# 04-RFID.net
KiCad netlist of a schematic drawn in Altium Designer
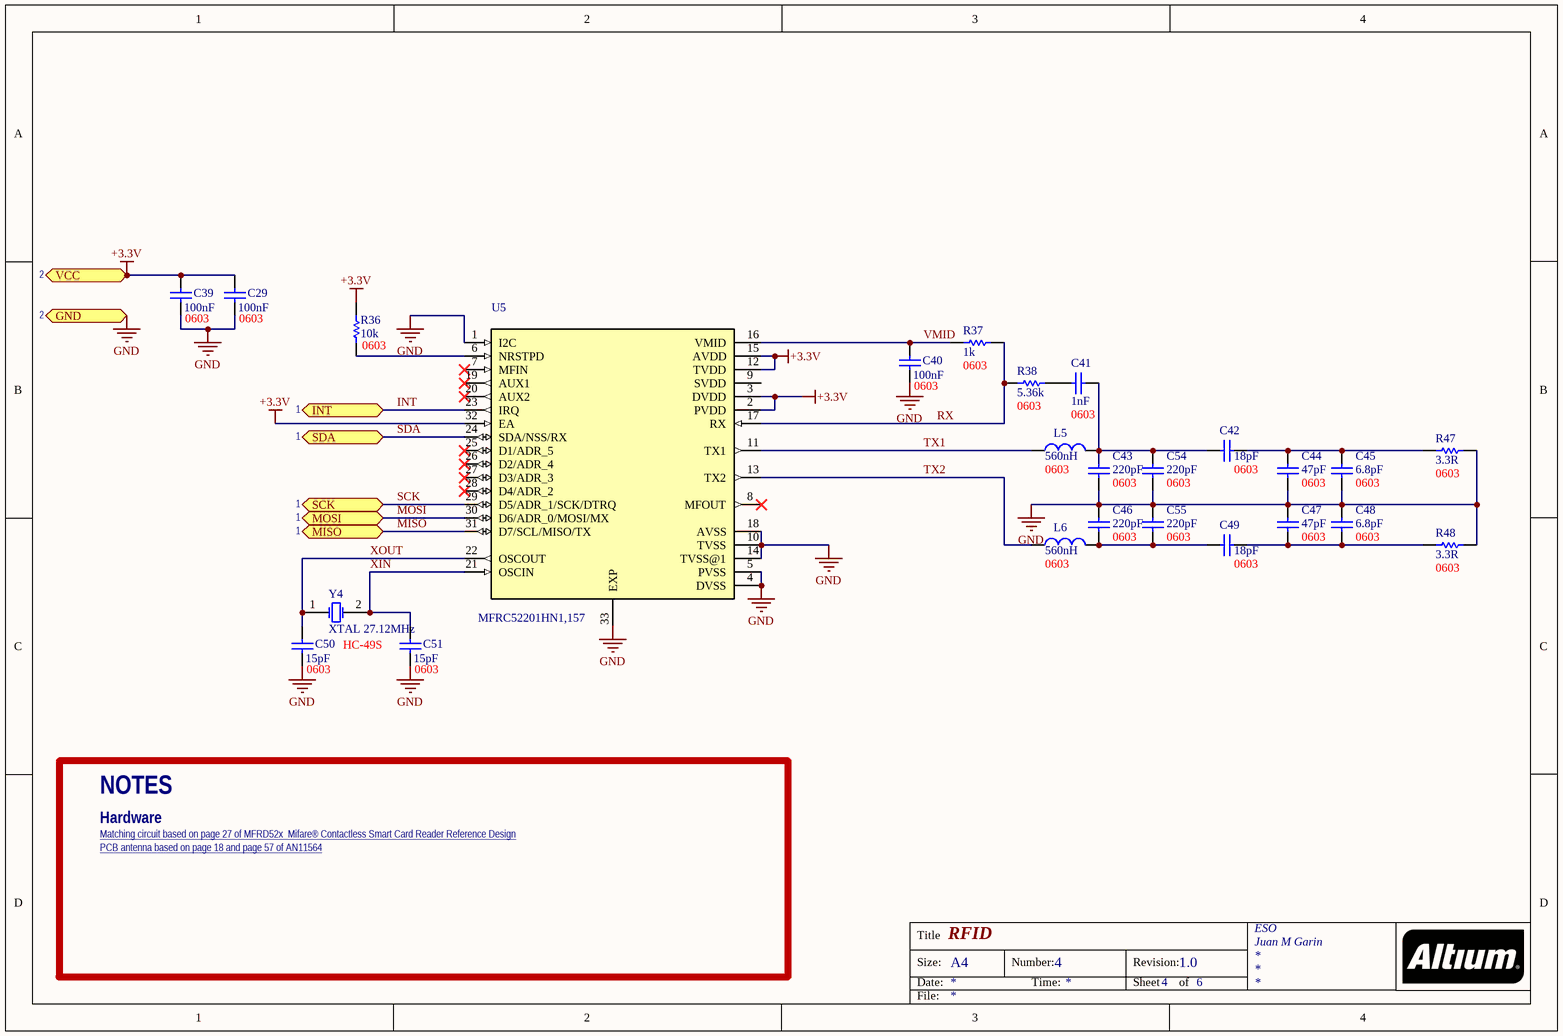
[diagram p0: 04-RFID.SchDoc]

(export (version "E")
  (design (tool "Eeschema 10.0.6"))
  (components
    (comp (ref "C29")
      (value "100nF")
      (footprint "C0603")
      (description "Capacitor (Semiconductor SIM Model)")
      (fields
        (field (name "MANUFACTURER PART NUMBER") "CL10F104ZO8NNNC")
        (field (name "PACKAGEREFERENCE") "0603")
      )
      (libsource (lib "Miscellaneous Devices") (part "Cap Semi"))
    )
    (comp (ref "C39")
      (value "100nF")
      (footprint "C0603")
      (description "Capacitor (Semiconductor SIM Model)")
      (fields
        (field (name "MANUFACTURER PART NUMBER") "CL10F104ZO8NNNC")
        (field (name "PACKAGEREFERENCE") "0603")
      )
      (libsource (lib "Miscellaneous Devices") (part "Cap Semi"))
    )
    (comp (ref "C40")
      (value "100nF")
      (footprint "C0603")
      (description "Capacitor (Semiconductor SIM Model)")
      (fields
        (field (name "MANUFACTURER PART NUMBER") "CL10F104ZO8NNNC")
        (field (name "PACKAGEREFERENCE") "0603")
      )
      (libsource (lib "Miscellaneous Devices") (part "Cap Semi"))
    )
    (comp (ref "C41")
      (value "1nF")
      (footprint "C0603")
      (description "Capacitor (Semiconductor SIM Model)")
      (fields
        (field (name "MANUFACTURER PART NUMBER") "CL10B102JB8NNNC")
        (field (name "PACKAGEREFERENCE") "0603")
      )
      (libsource (lib "Miscellaneous Devices") (part "Cap Semi"))
    )
    (comp (ref "C42")
      (value "18pF")
      (footprint "C0603")
      (description "Capacitor (Semiconductor SIM Model)")
      (fields
        (field (name "MANUFACTURER PART NUMBER") "VJ0603A180JXACW1BC")
        (field (name "PACKAGEREFERENCE") "0603")
      )
      (libsource (lib "Miscellaneous Devices") (part "Cap Semi"))
    )
    (comp (ref "C43")
      (value "220pF")
      (footprint "C0603")
      (description "Capacitor (Semiconductor SIM Model)")
      (fields
        (field (name "MANUFACTURER PART NUMBER") "885012206030")
        (field (name "PACKAGEREFERENCE") "0603")
      )
      (libsource (lib "Miscellaneous Devices") (part "Cap Semi"))
    )
    (comp (ref "C44")
      (value "47pF")
      (footprint "C0603")
      (description "Capacitor (Semiconductor SIM Model)")
      (fields
        (field (name "MANUFACTURER PART NUMBER") "885012006021")
        (field (name "PACKAGEREFERENCE") "0603")
      )
      (libsource (lib "Miscellaneous Devices") (part "Cap Semi"))
    )
    (comp (ref "C45")
      (value "6.8pF")
      (footprint "C0603")
      (description "Capacitor (Semiconductor SIM Model)")
      (fields
        (field (name "MANUFACTURER PART NUMBER") "CL10C6R8DB8NNNC")
        (field (name "PACKAGEREFERENCE") "0603")
      )
      (libsource (lib "Miscellaneous Devices") (part "Cap Semi"))
    )
    (comp (ref "C46")
      (value "220pF")
      (footprint "C0603")
      (description "Capacitor (Semiconductor SIM Model)")
      (fields
        (field (name "MANUFACTURER PART NUMBER") "885012206030")
        (field (name "PACKAGEREFERENCE") "0603")
      )
      (libsource (lib "Miscellaneous Devices") (part "Cap Semi"))
    )
    (comp (ref "C47")
      (value "47pF")
      (footprint "C0603")
      (description "Capacitor (Semiconductor SIM Model)")
      (fields
        (field (name "MANUFACTURER PART NUMBER") "885012006021")
        (field (name "PACKAGEREFERENCE") "0603")
      )
      (libsource (lib "Miscellaneous Devices") (part "Cap Semi"))
    )
    (comp (ref "C48")
      (value "6.8pF")
      (footprint "C0603")
      (description "Capacitor (Semiconductor SIM Model)")
      (fields
        (field (name "MANUFACTURER PART NUMBER") "CL10C6R8DB8NNNC")
        (field (name "PACKAGEREFERENCE") "0603")
      )
      (libsource (lib "Miscellaneous Devices") (part "Cap Semi"))
    )
    (comp (ref "C49")
      (value "18pF")
      (footprint "C0603")
      (description "Capacitor (Semiconductor SIM Model)")
      (fields
        (field (name "MANUFACTURER PART NUMBER") "VJ0603A180JXACW1BC")
        (field (name "PACKAGEREFERENCE") "0603")
      )
      (libsource (lib "Miscellaneous Devices") (part "Cap Semi"))
    )
    (comp (ref "C50")
      (value "15pF")
      (footprint "C0603")
      (description "Capacitor (Semiconductor SIM Model)")
      (fields
        (field (name "MANUFACTURER PART NUMBER") "CL10C150JC8NNNC")
        (field (name "PACKAGEREFERENCE") "0603")
      )
      (libsource (lib "Miscellaneous Devices") (part "Cap Semi"))
    )
    (comp (ref "C51")
      (value "15pF")
      (footprint "C0603")
      (description "Capacitor (Semiconductor SIM Model)")
      (fields
        (field (name "MANUFACTURER PART NUMBER") "CL10C150JC8NNNC")
        (field (name "PACKAGEREFERENCE") "0603")
      )
      (libsource (lib "Miscellaneous Devices") (part "Cap Semi"))
    )
    (comp (ref "C54")
      (value "220pF")
      (footprint "C0603")
      (description "Capacitor (Semiconductor SIM Model)")
      (fields
        (field (name "MANUFACTURER PART NUMBER") "885012206030")
        (field (name "PACKAGEREFERENCE") "0603")
      )
      (libsource (lib "Miscellaneous Devices") (part "Cap Semi"))
    )
    (comp (ref "C55")
      (value "220pF")
      (footprint "C0603")
      (description "Capacitor (Semiconductor SIM Model)")
      (fields
        (field (name "MANUFACTURER PART NUMBER") "885012206030")
        (field (name "PACKAGEREFERENCE") "0603")
      )
      (libsource (lib "Miscellaneous Devices") (part "Cap Semi"))
    )
    (comp (ref "L5")
      (value "560nH")
      (footprint "L0603")
      (description "Inductor")
      (fields
        (field (name "MANUFACTURER PART NUMBER") "AIML-0603-R56K-T")
        (field (name "PACKAGEREFERENCE") "0603")
      )
      (libsource (lib "schematic_library") (part "Inductor_0603"))
    )
    (comp (ref "L6")
      (value "560nH")
      (footprint "L0603")
      (description "Inductor")
      (fields
        (field (name "MANUFACTURER PART NUMBER") "AIML-0603-R56K-T")
        (field (name "PACKAGEREFERENCE") "0603")
      )
      (libsource (lib "schematic_library") (part "Inductor_0603"))
    )
    (comp (ref "R36")
      (value "10k")
      (footprint "R0603")
      (description "Resistor")
      (fields
        (field (name "MANUFACTURER PART NUMBER") "RMCF0603FT10K0")
        (field (name "PACKAGEREFERENCE") "0603")
      )
      (libsource (lib "Miscellaneous Devices") (part "Res1"))
    )
    (comp (ref "R37")
      (value "1k")
      (footprint "R0603")
      (description "Resistor")
      (fields
        (field (name "MANUFACTURER PART NUMBER") "RMCF0603FG1K00")
        (field (name "PACKAGEREFERENCE") "0603")
      )
      (libsource (lib "Miscellaneous Devices") (part "Res1"))
    )
    (comp (ref "R38")
      (value "5.36k")
      (footprint "R0603")
      (description "Resistor")
      (fields
        (field (name "MANUFACTURER PART NUMBER") "CR0603-FX-5361ELF")
        (field (name "PACKAGEREFERENCE") "0603")
      )
      (libsource (lib "Miscellaneous Devices") (part "Res1"))
    )
    (comp (ref "R47")
      (value "3.3R")
      (footprint "R0603")
      (description "Resistor")
      (fields
        (field (name "MANUFACTURER PART NUMBER") "CRGCQ0603J3R3")
        (field (name "PACKAGEREFERENCE") "0603")
      )
      (libsource (lib "Miscellaneous Devices") (part "Res1"))
    )
    (comp (ref "R48")
      (value "3.3R")
      (footprint "R0603")
      (description "Resistor")
      (fields
        (field (name "MANUFACTURER PART NUMBER") "CRGCQ0603J3R3")
        (field (name "PACKAGEREFERENCE") "0603")
      )
      (libsource (lib "Miscellaneous Devices") (part "Res1"))
    )
    (comp (ref "U5")
      (value "MFRC52201HN1,157")
      (footprint "QFN-32_5x5_0.5")
      (description "MFRC52201 Series 2.5 V - 3.6 V 27.12 MHz IC Smart Card Reader - HVQFN-32")
      (fields (field (name "MF") "NXP Semiconductors"))
      (libsource (lib "Library") (part "MFRC52201HN1,157"))
    )
    (comp (ref "Y4")
      (value "XTAL 27.12MHz")
      (footprint "XTAL-SMD")
      (description "Crystal Oscillator 27.12MHz SMD")
      (fields
        (field (name "MANUFACTURER PART NUMBER") "9C-27.120MAAJ-T")
        (field (name "PACKAGEREFERENCE") "HC-49S")
      )
      (libsource (lib "Library_Scott") (part "XTAL 16MHz"))
    )
  )
  (nets
    (net (code "1") (name "+3.3V") (class "Default")
      (node (ref "C29") (pin "2") (pinfunction "2_2") (pintype "passive"))
      (node (ref "C39") (pin "2") (pinfunction "2_2") (pintype "passive"))
      (node (ref "R36") (pin "1") (pinfunction "1_1") (pintype "passive"))
      (node (ref "U5") (pin "12") (pinfunction "TVDD_12") (pintype "power_in"))
      (node (ref "U5") (pin "15") (pinfunction "AVDD_15") (pintype "power_in"))
      (node (ref "U5") (pin "2") (pinfunction "PVDD_2") (pintype "power_in"))
      (node (ref "U5") (pin "3") (pinfunction "DVDD_3") (pintype "power_in"))
      (node (ref "U5") (pin "32") (pinfunction "EA_32") (pintype "input"))
    )
    (net (code "2") (name "/INT") (class "Default")
      (node (ref "U5") (pin "23") (pinfunction "IRQ_23") (pintype "output"))
    )
    (net (code "3") (name "/MISO") (class "Default")
      (node (ref "U5") (pin "31") (pinfunction "D7/SCL/MISO/TX_31") (pintype "bidirectional"))
    )
    (net (code "4") (name "/MOSI") (class "Default")
      (node (ref "U5") (pin "30") (pinfunction "D6/ADR_0/MOSI/MX_30") (pintype "bidirectional"))
    )
    (net (code "5") (name "/RX") (class "Default")
      (node (ref "R37") (pin "2") (pinfunction "2_2") (pintype "passive"))
      (node (ref "R38") (pin "1") (pinfunction "1_1") (pintype "passive"))
      (node (ref "U5") (pin "17") (pinfunction "RX_17") (pintype "input"))
    )
    (net (code "6") (name "/SCK") (class "Default")
      (node (ref "U5") (pin "29") (pinfunction "D5/ADR_1/SCK/DTRQ_29") (pintype "bidirectional"))
    )
    (net (code "7") (name "/SDA") (class "Default")
      (node (ref "U5") (pin "24") (pinfunction "SDA/NSS/RX_24") (pintype "bidirectional"))
    )
    (net (code "8") (name "/TX1") (class "Default")
      (node (ref "L5") (pin "1") (pinfunction "1_1") (pintype "passive"))
      (node (ref "U5") (pin "11") (pinfunction "TX1_11") (pintype "output"))
    )
    (net (code "9") (name "/TX2") (class "Default")
      (node (ref "L6") (pin "1") (pinfunction "1_1") (pintype "passive"))
      (node (ref "U5") (pin "13") (pinfunction "TX2_13") (pintype "output"))
    )
    (net (code "10") (name "/VMID") (class "Default")
      (node (ref "C40") (pin "2") (pinfunction "2_2") (pintype "passive"))
      (node (ref "R37") (pin "1") (pinfunction "1_1") (pintype "passive"))
      (node (ref "U5") (pin "16") (pinfunction "VMID_16") (pintype "power_in"))
    )
    (net (code "11") (name "/XIN") (class "Default")
      (node (ref "C51") (pin "2") (pinfunction "2_2") (pintype "passive"))
      (node (ref "U5") (pin "21") (pinfunction "OSCIN_21") (pintype "input"))
      (node (ref "Y4") (pin "2") (pinfunction "OSC2_2") (pintype "passive"))
    )
    (net (code "12") (name "/XOUT") (class "Default")
      (node (ref "C50") (pin "2") (pinfunction "2_2") (pintype "passive"))
      (node (ref "U5") (pin "22") (pinfunction "OSCOUT_22") (pintype "output"))
      (node (ref "Y4") (pin "1") (pinfunction "OSC1_1") (pintype "passive"))
    )
    (net (code "13") (name "GND") (class "Default")
      (node (ref "C29") (pin "1") (pinfunction "1_1") (pintype "passive"))
      (node (ref "C39") (pin "1") (pinfunction "1_1") (pintype "passive"))
      (node (ref "C40") (pin "1") (pinfunction "1_1") (pintype "passive"))
      (node (ref "C43") (pin "2") (pinfunction "2_2") (pintype "passive"))
      (node (ref "C44") (pin "2") (pinfunction "2_2") (pintype "passive"))
      (node (ref "C45") (pin "2") (pinfunction "2_2") (pintype "passive"))
      (node (ref "C46") (pin "1") (pinfunction "1_1") (pintype "passive"))
      (node (ref "C47") (pin "1") (pinfunction "1_1") (pintype "passive"))
      (node (ref "C48") (pin "1") (pinfunction "1_1") (pintype "passive"))
      (node (ref "C50") (pin "1") (pinfunction "1_1") (pintype "passive"))
      (node (ref "C51") (pin "1") (pinfunction "1_1") (pintype "passive"))
      (node (ref "C54") (pin "2") (pinfunction "2_2") (pintype "passive"))
      (node (ref "C55") (pin "1") (pinfunction "1_1") (pintype "passive"))
      (node (ref "R47") (pin "2") (pinfunction "2_2") (pintype "passive"))
      (node (ref "R48") (pin "2") (pinfunction "2_2") (pintype "passive"))
      (node (ref "U5") (pin "1") (pinfunction "I2C_1") (pintype "input"))
      (node (ref "U5") (pin "10") (pinfunction "TVSS_10") (pintype "power_in"))
      (node (ref "U5") (pin "14") (pinfunction "TVSS@1_14") (pintype "power_in"))
      (node (ref "U5") (pin "18") (pinfunction "AVSS_18") (pintype "power_in"))
      (node (ref "U5") (pin "33") (pinfunction "EXP_33") (pintype "power_in"))
      (node (ref "U5") (pin "4") (pinfunction "DVSS_4") (pintype "power_in"))
      (node (ref "U5") (pin "5") (pinfunction "PVSS_5") (pintype "power_in"))
    )
    (net (code "14") (name "Net-(C41-Pad1)") (class "Default")
      (node (ref "C41") (pin "1") (pinfunction "1_1") (pintype "passive"))
      (node (ref "C42") (pin "2") (pinfunction "2_2") (pintype "passive"))
      (node (ref "C43") (pin "1") (pinfunction "1_1") (pintype "passive"))
      (node (ref "C54") (pin "1") (pinfunction "1_1") (pintype "passive"))
      (node (ref "L5") (pin "2") (pinfunction "2_2") (pintype "passive"))
    )
    (net (code "15") (name "Net-(C41-Pad2)") (class "Default")
      (node (ref "C41") (pin "2") (pinfunction "2_2") (pintype "passive"))
      (node (ref "R38") (pin "2") (pinfunction "2_2") (pintype "passive"))
    )
    (net (code "16") (name "Net-(C42-Pad1)") (class "Default")
      (node (ref "C42") (pin "1") (pinfunction "1_1") (pintype "passive"))
      (node (ref "C44") (pin "1") (pinfunction "1_1") (pintype "passive"))
      (node (ref "C45") (pin "1") (pinfunction "1_1") (pintype "passive"))
      (node (ref "R47") (pin "1") (pinfunction "1_1") (pintype "passive"))
    )
    (net (code "17") (name "Net-(C46-Pad2)") (class "Default")
      (node (ref "C46") (pin "2") (pinfunction "2_2") (pintype "passive"))
      (node (ref "C49") (pin "2") (pinfunction "2_2") (pintype "passive"))
      (node (ref "C55") (pin "2") (pinfunction "2_2") (pintype "passive"))
      (node (ref "L6") (pin "2") (pinfunction "2_2") (pintype "passive"))
    )
    (net (code "18") (name "Net-(C47-Pad2)") (class "Default")
      (node (ref "C47") (pin "2") (pinfunction "2_2") (pintype "passive"))
      (node (ref "C48") (pin "2") (pinfunction "2_2") (pintype "passive"))
      (node (ref "C49") (pin "1") (pinfunction "1_1") (pintype "passive"))
      (node (ref "R48") (pin "1") (pinfunction "1_1") (pintype "passive"))
    )
    (net (code "19") (name "Net-(U5-NRSTPD)") (class "Default")
      (node (ref "R36") (pin "2") (pinfunction "2_2") (pintype "passive"))
      (node (ref "U5") (pin "6") (pinfunction "NRSTPD_6") (pintype "input"))
    )
    (net (code "20") (name "unconnected-(U5-AUX1-Pad19)") (class "Default")
      (node (ref "U5") (pin "19") (pinfunction "AUX1_19") (pintype "output+no_connect"))
    )
    (net (code "21") (name "unconnected-(U5-AUX2-Pad20)") (class "Default")
      (node (ref "U5") (pin "20") (pinfunction "AUX2_20") (pintype "output+no_connect"))
    )
    (net (code "22") (name "unconnected-(U5-D1{slash}ADR_5-Pad25)") (class "Default")
      (node (ref "U5") (pin "25") (pinfunction "D1/ADR_5_25") (pintype "bidirectional+no_connect"))
    )
    (net (code "23") (name "unconnected-(U5-D2{slash}ADR_4-Pad26)") (class "Default")
      (node (ref "U5") (pin "26") (pinfunction "D2/ADR_4_26") (pintype "bidirectional+no_connect"))
    )
    (net (code "24") (name "unconnected-(U5-D3{slash}ADR_3-Pad27)") (class "Default")
      (node (ref "U5") (pin "27") (pinfunction "D3/ADR_3_27") (pintype "bidirectional+no_connect"))
    )
    (net (code "25") (name "unconnected-(U5-D4{slash}ADR_2-Pad28)") (class "Default")
      (node (ref "U5") (pin "28") (pinfunction "D4/ADR_2_28") (pintype "bidirectional+no_connect"))
    )
    (net (code "26") (name "unconnected-(U5-MFIN-Pad7)") (class "Default")
      (node (ref "U5") (pin "7") (pinfunction "MFIN_7") (pintype "input+no_connect"))
    )
    (net (code "27") (name "unconnected-(U5-MFOUT-Pad8)") (class "Default")
      (node (ref "U5") (pin "8") (pinfunction "MFOUT_8") (pintype "output+no_connect"))
    )
    (net (code "28") (name "unconnected-(U5-SVDD-Pad9)") (class "Default")
      (node (ref "U5") (pin "9") (pinfunction "SVDD_9") (pintype "power_in"))
    )
  )
)
